# JTAG.net
KiCad netlist of a schematic drawn in EAGLE
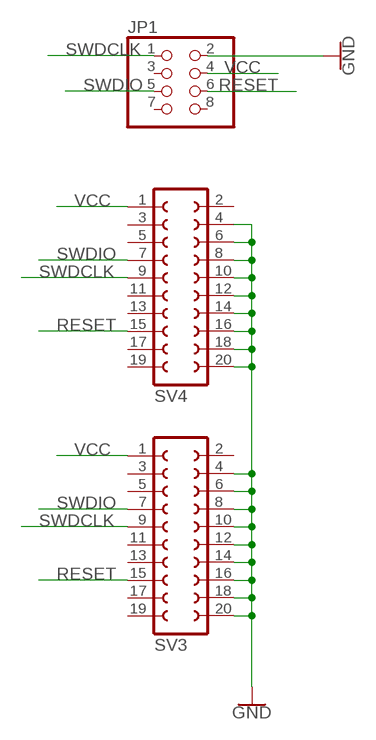
[diagram p0: schematic, sheet 1]

(export (version "E")
  (design (tool "Eeschema 10.0.6"))
  (components
    (comp (ref "JP1")
      (value "PINHD-2X4")
      (footprint "eagle-import:2X04")
      (libsource (lib "eagle-import") (part "PINHD-2X4"))
    )
    (comp (ref "SV3")
      (value "FE10-2")
      (footprint "eagle-import:FE10-2")
      (libsource (lib "eagle-import") (part "FE10-2"))
    )
    (comp (ref "SV4")
      (value "FE10-2")
      (footprint "eagle-import:FE10-2")
      (libsource (lib "eagle-import") (part "FE10-2"))
    )
  )
  (nets
    (net (code "1") (name "/RESET") (class "Default")
      (node (ref "JP1") (pin "6") (pinfunction "6_6") (pintype "passive"))
      (node (ref "SV3") (pin "15") (pinfunction "15_15") (pintype "passive"))
      (node (ref "SV4") (pin "15") (pinfunction "15_15") (pintype "passive"))
    )
    (net (code "2") (name "/SWDCLK") (class "Default")
      (node (ref "JP1") (pin "1") (pinfunction "1_1") (pintype "passive"))
      (node (ref "SV3") (pin "9") (pinfunction "9_9") (pintype "passive"))
      (node (ref "SV4") (pin "9") (pinfunction "9_9") (pintype "passive"))
    )
    (net (code "3") (name "/SWDIO") (class "Default")
      (node (ref "JP1") (pin "5") (pinfunction "5_5") (pintype "passive"))
      (node (ref "SV3") (pin "7") (pinfunction "7_7") (pintype "passive"))
      (node (ref "SV4") (pin "7") (pinfunction "7_7") (pintype "passive"))
    )
    (net (code "4") (name "/VCC") (class "Default")
      (node (ref "JP1") (pin "4") (pinfunction "4_4") (pintype "passive"))
      (node (ref "SV3") (pin "1") (pinfunction "1_1") (pintype "passive"))
      (node (ref "SV4") (pin "1") (pinfunction "1_1") (pintype "passive"))
    )
    (net (code "5") (name "GND") (class "Default")
      (node (ref "JP1") (pin "2") (pinfunction "2_2") (pintype "passive"))
      (node (ref "SV3") (pin "10") (pinfunction "10_10") (pintype "passive"))
      (node (ref "SV3") (pin "12") (pinfunction "12_12") (pintype "passive"))
      (node (ref "SV3") (pin "14") (pinfunction "14_14") (pintype "passive"))
      (node (ref "SV3") (pin "16") (pinfunction "16_16") (pintype "passive"))
      (node (ref "SV3") (pin "18") (pinfunction "18_18") (pintype "passive"))
      (node (ref "SV3") (pin "20") (pinfunction "20_20") (pintype "passive"))
      (node (ref "SV3") (pin "4") (pinfunction "4_4") (pintype "passive"))
      (node (ref "SV3") (pin "6") (pinfunction "6_6") (pintype "passive"))
      (node (ref "SV3") (pin "8") (pinfunction "8_8") (pintype "passive"))
      (node (ref "SV4") (pin "10") (pinfunction "10_10") (pintype "passive"))
      (node (ref "SV4") (pin "12") (pinfunction "12_12") (pintype "passive"))
      (node (ref "SV4") (pin "14") (pinfunction "14_14") (pintype "passive"))
      (node (ref "SV4") (pin "16") (pinfunction "16_16") (pintype "passive"))
      (node (ref "SV4") (pin "18") (pinfunction "18_18") (pintype "passive"))
      (node (ref "SV4") (pin "20") (pinfunction "20_20") (pintype "passive"))
      (node (ref "SV4") (pin "4") (pinfunction "4_4") (pintype "passive"))
      (node (ref "SV4") (pin "6") (pinfunction "6_6") (pintype "passive"))
      (node (ref "SV4") (pin "8") (pinfunction "8_8") (pintype "passive"))
    )
    (net (code "6") (name "unconnected-(JP1-Pad3)") (class "Default")
      (node (ref "JP1") (pin "3") (pinfunction "3_3") (pintype "passive"))
    )
    (net (code "7") (name "unconnected-(JP1-Pad7)") (class "Default")
      (node (ref "JP1") (pin "7") (pinfunction "7_7") (pintype "passive"))
    )
    (net (code "8") (name "unconnected-(JP1-Pad8)") (class "Default")
      (node (ref "JP1") (pin "8") (pinfunction "8_8") (pintype "passive"))
    )
    (net (code "9") (name "unconnected-(SV3-Pad2)") (class "Default")
      (node (ref "SV3") (pin "2") (pinfunction "2_2") (pintype "passive"))
    )
    (net (code "10") (name "unconnected-(SV3-Pad3)") (class "Default")
      (node (ref "SV3") (pin "3") (pinfunction "3_3") (pintype "passive"))
    )
    (net (code "11") (name "unconnected-(SV3-Pad5)") (class "Default")
      (node (ref "SV3") (pin "5") (pinfunction "5_5") (pintype "passive"))
    )
    (net (code "12") (name "unconnected-(SV3-Pad11)") (class "Default")
      (node (ref "SV3") (pin "11") (pinfunction "11_11") (pintype "passive"))
    )
    (net (code "13") (name "unconnected-(SV3-Pad13)") (class "Default")
      (node (ref "SV3") (pin "13") (pinfunction "13_13") (pintype "passive"))
    )
    (net (code "14") (name "unconnected-(SV3-Pad17)") (class "Default")
      (node (ref "SV3") (pin "17") (pinfunction "17_17") (pintype "passive"))
    )
    (net (code "15") (name "unconnected-(SV3-Pad19)") (class "Default")
      (node (ref "SV3") (pin "19") (pinfunction "19_19") (pintype "passive"))
    )
    (net (code "16") (name "unconnected-(SV4-Pad2)") (class "Default")
      (node (ref "SV4") (pin "2") (pinfunction "2_2") (pintype "passive"))
    )
    (net (code "17") (name "unconnected-(SV4-Pad3)") (class "Default")
      (node (ref "SV4") (pin "3") (pinfunction "3_3") (pintype "passive"))
    )
    (net (code "18") (name "unconnected-(SV4-Pad5)") (class "Default")
      (node (ref "SV4") (pin "5") (pinfunction "5_5") (pintype "passive"))
    )
    (net (code "19") (name "unconnected-(SV4-Pad11)") (class "Default")
      (node (ref "SV4") (pin "11") (pinfunction "11_11") (pintype "passive"))
    )
    (net (code "20") (name "unconnected-(SV4-Pad13)") (class "Default")
      (node (ref "SV4") (pin "13") (pinfunction "13_13") (pintype "passive"))
    )
    (net (code "21") (name "unconnected-(SV4-Pad17)") (class "Default")
      (node (ref "SV4") (pin "17") (pinfunction "17_17") (pintype "passive"))
    )
    (net (code "22") (name "unconnected-(SV4-Pad19)") (class "Default")
      (node (ref "SV4") (pin "19") (pinfunction "19_19") (pintype "passive"))
    )
  )
)
